# PLC-_-_-V1.net
KiCad netlist of a schematic drawn in Altium Designer
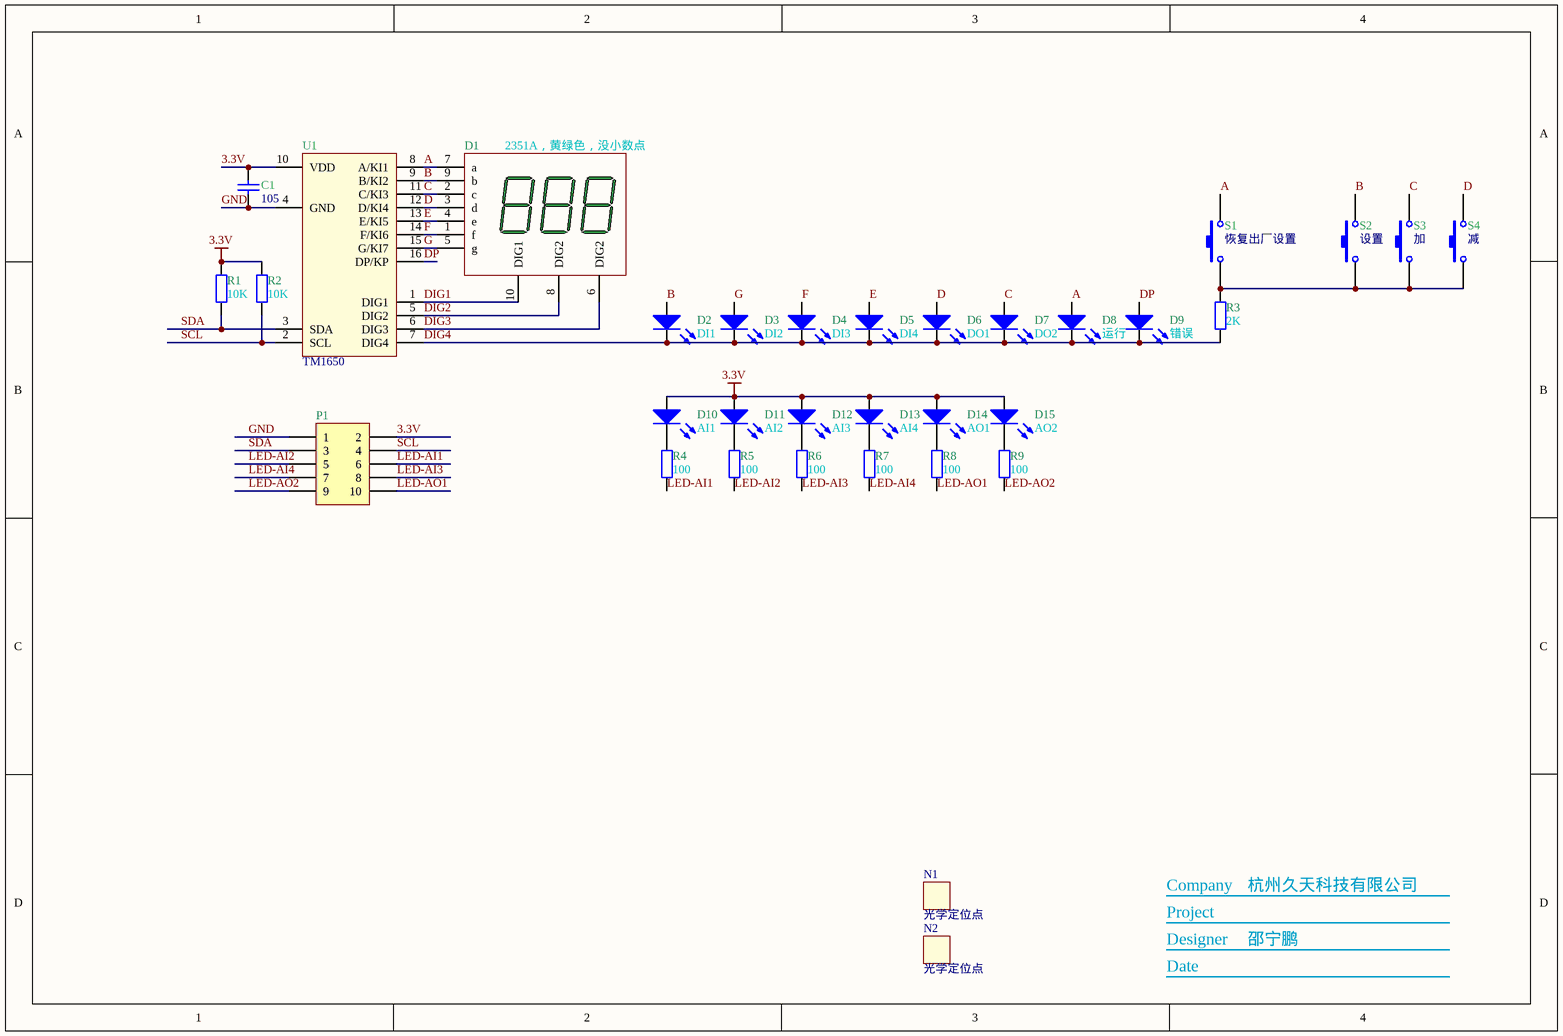
[diagram p0: PLC-无线通讯版-显示板-V1.SchDoc]

(export (version "E")
  (design (tool "Eeschema 10.0.6"))
  (components
    (comp (ref "C1")
      (value "105")
      (footprint "C-0603")
      (description "Capacitor")
      (fields (field (name "PUBLISHER") "Altium Limited"))
      (libsource (lib "元件2.0") (part "Cap"))
    )
    (comp (ref "D1")
      (value "2351A，黄绿色，没小数点")
      (footprint "3位0.25英寸")
      (libsource (lib "7显示屏-V1.0") (part "3位数码管-无点-2351A"))
    )
    (comp (ref "D2")
      (value "DI1")
      (footprint "LED-0603-GREEN")
      (fields (field (name "PUBLISHER") "Altium Limited"))
      (libsource (lib "4二极管-V1.1") (part "LED-0603-Blue"))
    )
    (comp (ref "D3")
      (value "DI2")
      (footprint "LED-0603-GREEN")
      (fields (field (name "PUBLISHER") "Altium Limited"))
      (libsource (lib "4二极管-V1.1") (part "LED-0603-Blue"))
    )
    (comp (ref "D4")
      (value "DI3")
      (footprint "LED-0603-GREEN")
      (fields (field (name "PUBLISHER") "Altium Limited"))
      (libsource (lib "4二极管-V1.1") (part "LED-0603-Blue"))
    )
    (comp (ref "D5")
      (value "DI4")
      (footprint "LED-0603-GREEN")
      (fields (field (name "PUBLISHER") "Altium Limited"))
      (libsource (lib "4二极管-V1.1") (part "LED-0603-Blue"))
    )
    (comp (ref "D6")
      (value "DO1")
      (footprint "LED-0603-GREEN")
      (fields (field (name "PUBLISHER") "Altium Limited"))
      (libsource (lib "4二极管-V1.1") (part "LED-0603-Blue"))
    )
    (comp (ref "D7")
      (value "DO2")
      (footprint "LED-0603-GREEN")
      (fields (field (name "PUBLISHER") "Altium Limited"))
      (libsource (lib "4二极管-V1.1") (part "LED-0603-Blue"))
    )
    (comp (ref "D8")
      (value "运行")
      (footprint "LED-0603-侧发光")
      (fields (field (name "PUBLISHER") "Altium Limited"))
      (libsource (lib "4二极管-V1.1") (part "LED-0603-Blue"))
    )
    (comp (ref "D9")
      (value "错误")
      (footprint "LED-0603-侧发光")
      (fields (field (name "PUBLISHER") "Altium Limited"))
      (libsource (lib "4二极管-V1.1") (part "LED-0603-Blue"))
    )
    (comp (ref "D10")
      (value "AI1")
      (footprint "LED-0603-GREEN")
      (fields (field (name "PUBLISHER") "Altium Limited"))
      (libsource (lib "4二极管-V1.1") (part "LED-0603-Blue"))
    )
    (comp (ref "D11")
      (value "AI2")
      (footprint "LED-0603-GREEN")
      (fields (field (name "PUBLISHER") "Altium Limited"))
      (libsource (lib "4二极管-V1.1") (part "LED-0603-Blue"))
    )
    (comp (ref "D12")
      (value "AI3")
      (footprint "LED-0603-GREEN")
      (fields (field (name "PUBLISHER") "Altium Limited"))
      (libsource (lib "4二极管-V1.1") (part "LED-0603-Blue"))
    )
    (comp (ref "D13")
      (value "AI4")
      (footprint "LED-0603-GREEN")
      (fields (field (name "PUBLISHER") "Altium Limited"))
      (libsource (lib "4二极管-V1.1") (part "LED-0603-Blue"))
    )
    (comp (ref "D14")
      (value "AO1")
      (footprint "LED-0603-GREEN")
      (fields (field (name "PUBLISHER") "Altium Limited"))
      (libsource (lib "4二极管-V1.1") (part "LED-0603-Blue"))
    )
    (comp (ref "D15")
      (value "AO2")
      (footprint "LED-0603-GREEN")
      (fields (field (name "PUBLISHER") "Altium Limited"))
      (libsource (lib "4二极管-V1.1") (part "LED-0603-Blue"))
    )
    (comp (ref "N1") (value "光学定位点") (footprint "MARK-1mm-3mm") (libsource (lib "11其他元件-V1.0") (part "无引脚")))
    (comp (ref "N2") (value "光学定位点") (footprint "MARK-1mm-3mm") (libsource (lib "11其他元件-V1.0") (part "无引脚")))
    (comp (ref "P1")
      (value "~")
      (footprint "HDR2X5-贴片母座")
      (description "Header, 5-Pin, Dual row")
      (fields (field (name "PUBLISHER") "Altium Limited"))
      (libsource (lib "5排针-V1.0") (part "Header 5X2"))
    )
    (comp (ref "R1")
      (value "10K")
      (footprint "R-0603")
      (description "0603")
      (fields (field (name "PUBLISHER") "Altium Limited"))
      (libsource (lib "1电阻-V1.0") (part "Res2-0603"))
    )
    (comp (ref "R2")
      (value "10K")
      (footprint "R-0603")
      (description "0603")
      (fields (field (name "PUBLISHER") "Altium Limited"))
      (libsource (lib "1电阻-V1.0") (part "Res2-0603"))
    )
    (comp (ref "R3")
      (value "2K")
      (footprint "R-0603")
      (description "0603")
      (fields (field (name "PUBLISHER") "Altium Limited"))
      (libsource (lib "1电阻-V1.0") (part "Res2-0603"))
    )
    (comp (ref "R4")
      (value "100")
      (footprint "R-0603")
      (description "0603")
      (fields (field (name "PUBLISHER") "Altium Limited"))
      (libsource (lib "1电阻-V1.0") (part "Res2-0603"))
    )
    (comp (ref "R5")
      (value "100")
      (footprint "R-0603")
      (description "0603")
      (fields (field (name "PUBLISHER") "Altium Limited"))
      (libsource (lib "1电阻-V1.0") (part "Res2-0603"))
    )
    (comp (ref "R6")
      (value "100")
      (footprint "R-0603")
      (description "0603")
      (fields (field (name "PUBLISHER") "Altium Limited"))
      (libsource (lib "1电阻-V1.0") (part "Res2-0603"))
    )
    (comp (ref "R7")
      (value "100")
      (footprint "R-0603")
      (description "0603")
      (fields (field (name "PUBLISHER") "Altium Limited"))
      (libsource (lib "1电阻-V1.0") (part "Res2-0603"))
    )
    (comp (ref "R8")
      (value "100")
      (footprint "R-0603")
      (description "0603")
      (fields (field (name "PUBLISHER") "Altium Limited"))
      (libsource (lib "1电阻-V1.0") (part "Res2-0603"))
    )
    (comp (ref "R9")
      (value "100")
      (footprint "R-0603")
      (description "0603")
      (fields (field (name "PUBLISHER") "Altium Limited"))
      (libsource (lib "1电阻-V1.0") (part "Res2-0603"))
    )
    (comp (ref "S1")
      (value "恢复出厂设置")
      (footprint "SB-6*6*9.5_贴片")
      (description "SB-6*6*10")
      (fields (field (name "PUBLISHER") "Altium Limited"))
      (libsource (lib "开关-V1") (part "SB-6*6*9"))
    )
    (comp (ref "S2")
      (value "设置")
      (footprint "SB-6*6*9.5_贴片")
      (description "SB-6*6*10")
      (fields (field (name "PUBLISHER") "Altium Limited"))
      (libsource (lib "开关-V1") (part "SB-6*6*9"))
    )
    (comp (ref "S3")
      (value "加")
      (footprint "SB-6*6*9.5_贴片")
      (description "SB-6*6*10")
      (fields (field (name "PUBLISHER") "Altium Limited"))
      (libsource (lib "开关-V1") (part "SB-6*6*9"))
    )
    (comp (ref "S4")
      (value "减")
      (footprint "SB-6*6*9.5_贴片")
      (description "SB-6*6*10")
      (fields (field (name "PUBLISHER") "Altium Limited"))
      (libsource (lib "开关-V1") (part "SB-6*6*9"))
    )
    (comp (ref "U1")
      (value "TM1650")
      (footprint "SOP-16-M")
      (description "共阴数码管驱动器")
      (libsource (lib "8集成电路-V1.1") (part "TM1650"))
    )
  )
  (nets
    (net (code "1") (name "/A") (class "Default")
      (node (ref "D1") (pin "7") (pinfunction "a_7") (pintype "passive"))
      (node (ref "D8") (pin "1") (pinfunction "A_1") (pintype "passive"))
      (node (ref "S1") (pin "2") (pinfunction "2_2") (pintype "passive"))
      (node (ref "U1") (pin "8") (pinfunction "A/KI1_8") (pintype "passive"))
    )
    (net (code "2") (name "/B") (class "Default")
      (node (ref "D1") (pin "9") (pinfunction "b_9") (pintype "passive"))
      (node (ref "D2") (pin "1") (pinfunction "A_1") (pintype "passive"))
      (node (ref "S2") (pin "2") (pinfunction "2_2") (pintype "passive"))
      (node (ref "U1") (pin "9") (pinfunction "B/KI2_9") (pintype "passive"))
    )
    (net (code "3") (name "/C") (class "Default")
      (node (ref "D1") (pin "2") (pinfunction "c_2") (pintype "passive"))
      (node (ref "D7") (pin "1") (pinfunction "A_1") (pintype "passive"))
      (node (ref "S3") (pin "2") (pinfunction "2_2") (pintype "passive"))
      (node (ref "U1") (pin "11") (pinfunction "C/KI3_11") (pintype "passive"))
    )
    (net (code "4") (name "/D") (class "Default")
      (node (ref "D1") (pin "3") (pinfunction "d_3") (pintype "passive"))
      (node (ref "D6") (pin "1") (pinfunction "A_1") (pintype "passive"))
      (node (ref "S4") (pin "2") (pinfunction "2_2") (pintype "passive"))
      (node (ref "U1") (pin "12") (pinfunction "D/KI4_12") (pintype "passive"))
    )
    (net (code "5") (name "/DIG1") (class "Default")
      (node (ref "D1") (pin "10") (pinfunction "DIG1_10") (pintype "passive"))
      (node (ref "U1") (pin "1") (pinfunction "DIG1_1") (pintype "passive"))
    )
    (net (code "6") (name "/DIG2") (class "Default")
      (node (ref "D1") (pin "8") (pinfunction "DIG2_8") (pintype "passive"))
      (node (ref "U1") (pin "5") (pinfunction "DIG2_5") (pintype "passive"))
    )
    (net (code "7") (name "/DIG3") (class "Default")
      (node (ref "D1") (pin "6") (pinfunction "DIG2_6") (pintype "passive"))
      (node (ref "U1") (pin "6") (pinfunction "DIG3_6") (pintype "passive"))
    )
    (net (code "8") (name "/DIG4") (class "Default")
      (node (ref "D2") (pin "2") (pinfunction "K_2") (pintype "passive"))
      (node (ref "D3") (pin "2") (pinfunction "K_2") (pintype "passive"))
      (node (ref "D4") (pin "2") (pinfunction "K_2") (pintype "passive"))
      (node (ref "D5") (pin "2") (pinfunction "K_2") (pintype "passive"))
      (node (ref "D6") (pin "2") (pinfunction "K_2") (pintype "passive"))
      (node (ref "D7") (pin "2") (pinfunction "K_2") (pintype "passive"))
      (node (ref "D8") (pin "2") (pinfunction "K_2") (pintype "passive"))
      (node (ref "D9") (pin "2") (pinfunction "K_2") (pintype "passive"))
      (node (ref "R3") (pin "2") (pinfunction "2_2") (pintype "passive"))
      (node (ref "U1") (pin "7") (pinfunction "DIG4_7") (pintype "passive"))
    )
    (net (code "9") (name "/DP") (class "Default")
      (node (ref "D9") (pin "1") (pinfunction "A_1") (pintype "passive"))
      (node (ref "U1") (pin "16") (pinfunction "DP/KP_16") (pintype "passive"))
    )
    (net (code "10") (name "/E") (class "Default")
      (node (ref "D1") (pin "4") (pinfunction "e_4") (pintype "passive"))
      (node (ref "D5") (pin "1") (pinfunction "A_1") (pintype "passive"))
      (node (ref "U1") (pin "13") (pinfunction "E/KI5_13") (pintype "passive"))
    )
    (net (code "11") (name "/F") (class "Default")
      (node (ref "D1") (pin "1") (pinfunction "f_1") (pintype "passive"))
      (node (ref "D4") (pin "1") (pinfunction "A_1") (pintype "passive"))
      (node (ref "U1") (pin "14") (pinfunction "F/KI6_14") (pintype "passive"))
    )
    (net (code "12") (name "/G") (class "Default")
      (node (ref "D1") (pin "5") (pinfunction "g_5") (pintype "passive"))
      (node (ref "D3") (pin "1") (pinfunction "A_1") (pintype "passive"))
      (node (ref "U1") (pin "15") (pinfunction "G/KI7_15") (pintype "passive"))
    )
    (net (code "13") (name "/GND") (class "Default")
      (node (ref "C1") (pin "1") (pinfunction "1_1") (pintype "passive"))
      (node (ref "P1") (pin "1") (pinfunction "1_1") (pintype "passive"))
      (node (ref "U1") (pin "4") (pinfunction "GND_4") (pintype "passive"))
    )
    (net (code "14") (name "/LED-AI1") (class "Default")
      (node (ref "P1") (pin "6") (pinfunction "6_6") (pintype "passive"))
      (node (ref "R4") (pin "2") (pinfunction "2_2") (pintype "passive"))
    )
    (net (code "15") (name "/LED-AI2") (class "Default")
      (node (ref "P1") (pin "5") (pinfunction "5_5") (pintype "passive"))
      (node (ref "R5") (pin "2") (pinfunction "2_2") (pintype "passive"))
    )
    (net (code "16") (name "/LED-AI3") (class "Default")
      (node (ref "P1") (pin "8") (pinfunction "8_8") (pintype "passive"))
      (node (ref "R6") (pin "2") (pinfunction "2_2") (pintype "passive"))
    )
    (net (code "17") (name "/LED-AI4") (class "Default")
      (node (ref "P1") (pin "7") (pinfunction "7_7") (pintype "passive"))
      (node (ref "R7") (pin "2") (pinfunction "2_2") (pintype "passive"))
    )
    (net (code "18") (name "/LED-AO1") (class "Default")
      (node (ref "P1") (pin "10") (pinfunction "10_10") (pintype "passive"))
      (node (ref "R8") (pin "2") (pinfunction "2_2") (pintype "passive"))
    )
    (net (code "19") (name "/LED-AO2") (class "Default")
      (node (ref "P1") (pin "9") (pinfunction "9_9") (pintype "passive"))
      (node (ref "R9") (pin "2") (pinfunction "2_2") (pintype "passive"))
    )
    (net (code "20") (name "/SCL") (class "Default")
      (node (ref "P1") (pin "4") (pinfunction "4_4") (pintype "passive"))
      (node (ref "R2") (pin "2") (pinfunction "2_2") (pintype "passive"))
      (node (ref "U1") (pin "2") (pinfunction "SCL_2") (pintype "passive"))
    )
    (net (code "21") (name "/SDA") (class "Default")
      (node (ref "P1") (pin "3") (pinfunction "3_3") (pintype "passive"))
      (node (ref "R1") (pin "2") (pinfunction "2_2") (pintype "passive"))
      (node (ref "U1") (pin "3") (pinfunction "SDA_3") (pintype "passive"))
    )
    (net (code "22") (name "3.3V") (class "Default")
      (node (ref "C1") (pin "2") (pinfunction "2_2") (pintype "passive"))
      (node (ref "D10") (pin "1") (pinfunction "A_1") (pintype "passive"))
      (node (ref "D11") (pin "1") (pinfunction "A_1") (pintype "passive"))
      (node (ref "D12") (pin "1") (pinfunction "A_1") (pintype "passive"))
      (node (ref "D13") (pin "1") (pinfunction "A_1") (pintype "passive"))
      (node (ref "D14") (pin "1") (pinfunction "A_1") (pintype "passive"))
      (node (ref "D15") (pin "1") (pinfunction "A_1") (pintype "passive"))
      (node (ref "P1") (pin "2") (pinfunction "2_2") (pintype "passive"))
      (node (ref "R1") (pin "1") (pinfunction "1_1") (pintype "passive"))
      (node (ref "R2") (pin "1") (pinfunction "1_1") (pintype "passive"))
      (node (ref "U1") (pin "10") (pinfunction "VDD_10") (pintype "passive"))
    )
    (net (code "23") (name "Net-(D10-K)") (class "Default")
      (node (ref "D10") (pin "2") (pinfunction "K_2") (pintype "passive"))
      (node (ref "R4") (pin "1") (pinfunction "1_1") (pintype "passive"))
    )
    (net (code "24") (name "Net-(D11-K)") (class "Default")
      (node (ref "D11") (pin "2") (pinfunction "K_2") (pintype "passive"))
      (node (ref "R5") (pin "1") (pinfunction "1_1") (pintype "passive"))
    )
    (net (code "25") (name "Net-(D12-K)") (class "Default")
      (node (ref "D12") (pin "2") (pinfunction "K_2") (pintype "passive"))
      (node (ref "R6") (pin "1") (pinfunction "1_1") (pintype "passive"))
    )
    (net (code "26") (name "Net-(D13-K)") (class "Default")
      (node (ref "D13") (pin "2") (pinfunction "K_2") (pintype "passive"))
      (node (ref "R7") (pin "1") (pinfunction "1_1") (pintype "passive"))
    )
    (net (code "27") (name "Net-(D14-K)") (class "Default")
      (node (ref "D14") (pin "2") (pinfunction "K_2") (pintype "passive"))
      (node (ref "R8") (pin "1") (pinfunction "1_1") (pintype "passive"))
    )
    (net (code "28") (name "Net-(D15-K)") (class "Default")
      (node (ref "D15") (pin "2") (pinfunction "K_2") (pintype "passive"))
      (node (ref "R9") (pin "1") (pinfunction "1_1") (pintype "passive"))
    )
    (net (code "29") (name "Net-(R3-Pad1)") (class "Default")
      (node (ref "R3") (pin "1") (pinfunction "1_1") (pintype "passive"))
      (node (ref "S1") (pin "1") (pinfunction "1_1") (pintype "passive"))
      (node (ref "S2") (pin "1") (pinfunction "1_1") (pintype "passive"))
      (node (ref "S3") (pin "1") (pinfunction "1_1") (pintype "passive"))
      (node (ref "S4") (pin "1") (pinfunction "1_1") (pintype "passive"))
    )
  )
)
